# ExenMiniLighthouseShield.net
KiCad netlist of a schematic drawn in EAGLE
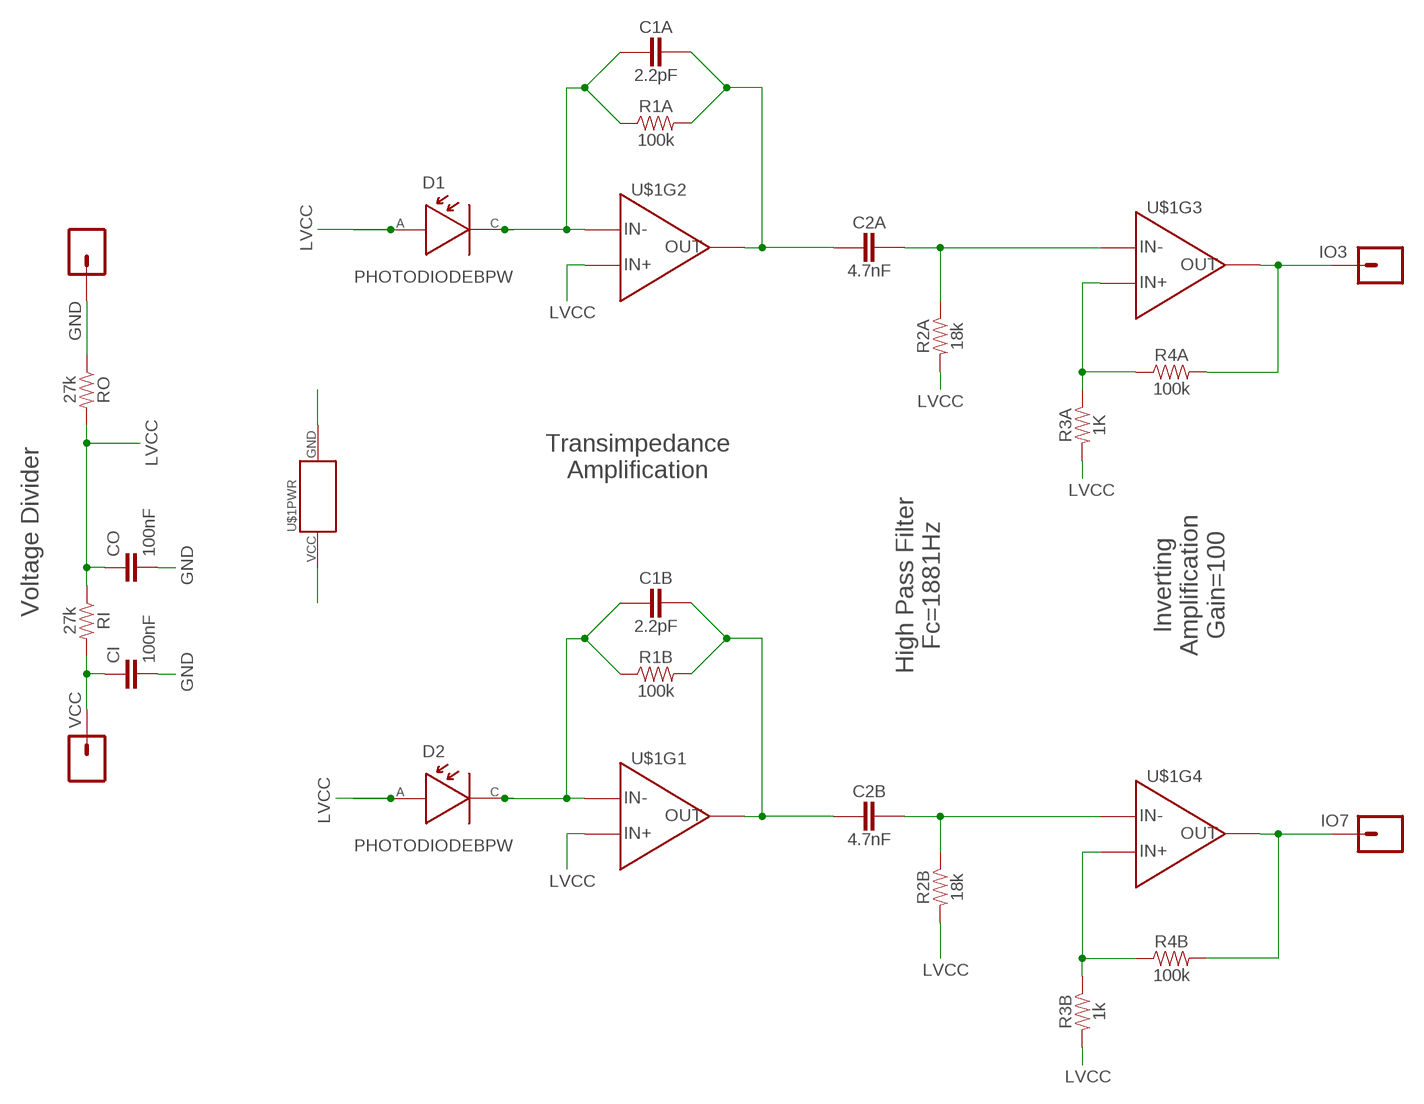
[diagram p0: schematic, sheet 1]

(export (version "E")
  (design (tool "Eeschema 10.0.6"))
  (components
    (comp (ref "C1A")
      (value "2.2pF")
      (footprint "eagle-import:PASSIVE-0603")
      (libsource (lib "eagle-import") (part "CAPACITOR"))
    )
    (comp (ref "C1B")
      (value "2.2pF")
      (footprint "eagle-import:PASSIVE-0603")
      (libsource (lib "eagle-import") (part "CAPACITOR"))
    )
    (comp (ref "C2A")
      (value "4.7nF")
      (footprint "eagle-import:PASSIVE-0603")
      (libsource (lib "eagle-import") (part "CAPACITOR"))
    )
    (comp (ref "C2B")
      (value "4.7nF")
      (footprint "eagle-import:PASSIVE-0603")
      (libsource (lib "eagle-import") (part "CAPACITOR"))
    )
    (comp (ref "CI")
      (value "100nF")
      (footprint "eagle-import:0603")
      (libsource (lib "eagle-import") (part "4.7PF-0603-50V-5%"))
    )
    (comp (ref "CO")
      (value "100nF")
      (footprint "eagle-import:0603")
      (libsource (lib "eagle-import") (part "4.7PF-0603-50V-5%"))
    )
    (comp (ref "D1")
      (value "PHOTODIODEBPW")
      (footprint "eagle-import:BPW34_BP104_SMD")
      (libsource (lib "eagle-import") (part "PHOTODIODEBPW"))
    )
    (comp (ref "D2")
      (value "PHOTODIODEBPW")
      (footprint "eagle-import:BPW34_BP104_SMD")
      (libsource (lib "eagle-import") (part "PHOTODIODEBPW"))
    )
    (comp (ref "GND")
      (value "SINGLE-THROUGH-HOLE")
      (footprint "eagle-import:SINGLE-THROUGH-HOLE")
      (libsource (lib "eagle-import") (part "SINGLE-THROUGH-HOLE"))
    )
    (comp (ref "IO3")
      (value "CONN_01PTH_NO_SILK_YES_STOP")
      (footprint "eagle-import:1X01_NO_SILK")
      (libsource (lib "eagle-import") (part "CONN_01PTH_NO_SILK_YES_STOP"))
    )
    (comp (ref "IO7")
      (value "CONN_01PTH_NO_SILK_YES_STOP")
      (footprint "eagle-import:1X01_NO_SILK")
      (libsource (lib "eagle-import") (part "CONN_01PTH_NO_SILK_YES_STOP"))
    )
    (comp (ref "R1A")
      (value "100k")
      (footprint "eagle-import:PASSIVE-0603")
      (libsource (lib "eagle-import") (part "RESISTOR"))
    )
    (comp (ref "R1B")
      (value "100k")
      (footprint "eagle-import:PASSIVE-0603")
      (libsource (lib "eagle-import") (part "RESISTOR"))
    )
    (comp (ref "R2A")
      (value "18k")
      (footprint "eagle-import:PASSIVE-0603")
      (libsource (lib "eagle-import") (part "RESISTOR"))
    )
    (comp (ref "R2B")
      (value "18k")
      (footprint "eagle-import:PASSIVE-0603")
      (libsource (lib "eagle-import") (part "RESISTOR"))
    )
    (comp (ref "R3A")
      (value "1K")
      (footprint "eagle-import:PASSIVE-0603")
      (libsource (lib "eagle-import") (part "RESISTOR"))
    )
    (comp (ref "R3B")
      (value "1k")
      (footprint "eagle-import:PASSIVE-0603")
      (libsource (lib "eagle-import") (part "RESISTOR"))
    )
    (comp (ref "R4A")
      (value "100k")
      (footprint "eagle-import:PASSIVE-0603")
      (libsource (lib "eagle-import") (part "RESISTOR"))
    )
    (comp (ref "R4B")
      (value "100k")
      (footprint "eagle-import:PASSIVE-0603")
      (libsource (lib "eagle-import") (part "RESISTOR"))
    )
    (comp (ref "RI")
      (value "27k")
      (footprint "eagle-import:0603")
      (libsource (lib "eagle-import") (part "100KOHM-0603-1/10W-1%"))
    )
    (comp (ref "RO")
      (value "27k")
      (footprint "eagle-import:0603")
      (libsource (lib "eagle-import") (part "100KOHM-0603-1/10W-1%"))
    )
    (comp (ref "U$1")
      (value "TLV2464IPW")
      (footprint "eagle-import:PW14")
      (libsource (lib "eagle-import") (part "TLV2464IPW"))
    )
    (comp (ref "VCC")
      (value "CONN_01PTH_NO_SILK_YES_STOP")
      (footprint "eagle-import:1X01_NO_SILK")
      (libsource (lib "eagle-import") (part "CONN_01PTH_NO_SILK_YES_STOP"))
    )
  )
  (nets
    (net (code "1") (name "/GND") (class "Default")
      (node (ref "CI") (pin "2") (pinfunction "2_2") (pintype "passive"))
      (node (ref "CO") (pin "2") (pinfunction "2_2") (pintype "passive"))
      (node (ref "GND") (pin "1") (pinfunction "1_1") (pintype "passive"))
      (node (ref "RO") (pin "1") (pinfunction "1_1") (pintype "passive"))
      (node (ref "U$1") (pin "11") (pinfunction "GND_11") (pintype "bidirectional"))
    )
    (net (code "2") (name "/IO3") (class "Default")
      (node (ref "IO3") (pin "1") (pinfunction "1_1") (pintype "passive"))
      (node (ref "R4A") (pin "2") (pinfunction "2_2") (pintype "passive"))
      (node (ref "U$1") (pin "8") (pinfunction "OUT_8") (pintype "bidirectional"))
    )
    (net (code "3") (name "/IO7") (class "Default")
      (node (ref "IO7") (pin "1") (pinfunction "1_1") (pintype "passive"))
      (node (ref "R4B") (pin "2") (pinfunction "2_2") (pintype "passive"))
      (node (ref "U$1") (pin "14") (pinfunction "OUT_14") (pintype "bidirectional"))
    )
    (net (code "4") (name "/LVCC") (class "Default")
      (node (ref "CO") (pin "1") (pinfunction "1_1") (pintype "passive"))
      (node (ref "D1") (pin "ANODE") (pinfunction "ANODE_ANODE") (pintype "bidirectional"))
      (node (ref "D2") (pin "ANODE") (pinfunction "ANODE_ANODE") (pintype "bidirectional"))
      (node (ref "R2A") (pin "2") (pinfunction "2_2") (pintype "passive"))
      (node (ref "R2B") (pin "2") (pinfunction "2_2") (pintype "passive"))
      (node (ref "R3A") (pin "2") (pinfunction "2_2") (pintype "passive"))
      (node (ref "R3B") (pin "2") (pinfunction "2_2") (pintype "passive"))
      (node (ref "RI") (pin "1") (pinfunction "1_1") (pintype "passive"))
      (node (ref "RO") (pin "2") (pinfunction "2_2") (pintype "passive"))
      (node (ref "U$1") (pin "3") (pinfunction "IN+_3") (pintype "bidirectional"))
      (node (ref "U$1") (pin "5") (pinfunction "IN+_5") (pintype "bidirectional"))
    )
    (net (code "5") (name "/VCC") (class "Default")
      (node (ref "CI") (pin "1") (pinfunction "1_1") (pintype "passive"))
      (node (ref "RI") (pin "2") (pinfunction "2_2") (pintype "passive"))
      (node (ref "U$1") (pin "4") (pinfunction "VCC_4") (pintype "bidirectional"))
      (node (ref "VCC") (pin "1") (pinfunction "1_1") (pintype "passive"))
    )
    (net (code "6") (name "Net-(U$1A-IN-)") (class "Default")
      (node (ref "C1B") (pin "1") (pinfunction "1_1") (pintype "passive"))
      (node (ref "D2") (pin "CATHODE") (pinfunction "CATHODE_CATHODE") (pintype "bidirectional"))
      (node (ref "R1B") (pin "1") (pinfunction "1_1") (pintype "passive"))
      (node (ref "U$1") (pin "2") (pinfunction "IN-_2") (pintype "bidirectional"))
    )
    (net (code "7") (name "Net-(U$1A-OUT)") (class "Default")
      (node (ref "C1B") (pin "2") (pinfunction "2_2") (pintype "passive"))
      (node (ref "C2B") (pin "1") (pinfunction "1_1") (pintype "passive"))
      (node (ref "R1B") (pin "2") (pinfunction "2_2") (pintype "passive"))
      (node (ref "U$1") (pin "1") (pinfunction "OUT_1") (pintype "bidirectional"))
    )
    (net (code "8") (name "Net-(U$1B-IN-)") (class "Default")
      (node (ref "C1A") (pin "1") (pinfunction "1_1") (pintype "passive"))
      (node (ref "D1") (pin "CATHODE") (pinfunction "CATHODE_CATHODE") (pintype "bidirectional"))
      (node (ref "R1A") (pin "1") (pinfunction "1_1") (pintype "passive"))
      (node (ref "U$1") (pin "6") (pinfunction "IN-_6") (pintype "bidirectional"))
    )
    (net (code "9") (name "Net-(U$1B-OUT)") (class "Default")
      (node (ref "C1A") (pin "2") (pinfunction "2_2") (pintype "passive"))
      (node (ref "C2A") (pin "1") (pinfunction "1_1") (pintype "passive"))
      (node (ref "R1A") (pin "2") (pinfunction "2_2") (pintype "passive"))
      (node (ref "U$1") (pin "7") (pinfunction "OUT_7") (pintype "bidirectional"))
    )
    (net (code "10") (name "Net-(U$1C-IN+)") (class "Default")
      (node (ref "R3A") (pin "1") (pinfunction "1_1") (pintype "passive"))
      (node (ref "R4A") (pin "1") (pinfunction "1_1") (pintype "passive"))
      (node (ref "U$1") (pin "10") (pinfunction "IN+_10") (pintype "bidirectional"))
    )
    (net (code "11") (name "Net-(U$1C-IN-)") (class "Default")
      (node (ref "C2A") (pin "2") (pinfunction "2_2") (pintype "passive"))
      (node (ref "R2A") (pin "1") (pinfunction "1_1") (pintype "passive"))
      (node (ref "U$1") (pin "9") (pinfunction "IN-_9") (pintype "bidirectional"))
    )
    (net (code "12") (name "Net-(U$1D-IN+)") (class "Default")
      (node (ref "R3B") (pin "1") (pinfunction "1_1") (pintype "passive"))
      (node (ref "R4B") (pin "1") (pinfunction "1_1") (pintype "passive"))
      (node (ref "U$1") (pin "12") (pinfunction "IN+_12") (pintype "bidirectional"))
    )
    (net (code "13") (name "Net-(U$1D-IN-)") (class "Default")
      (node (ref "C2B") (pin "2") (pinfunction "2_2") (pintype "passive"))
      (node (ref "R2B") (pin "1") (pinfunction "1_1") (pintype "passive"))
      (node (ref "U$1") (pin "13") (pinfunction "IN-_13") (pintype "bidirectional"))
    )
  )
)
